# InitialTransceivers.net
KiCad netlist of a schematic drawn in EAGLE
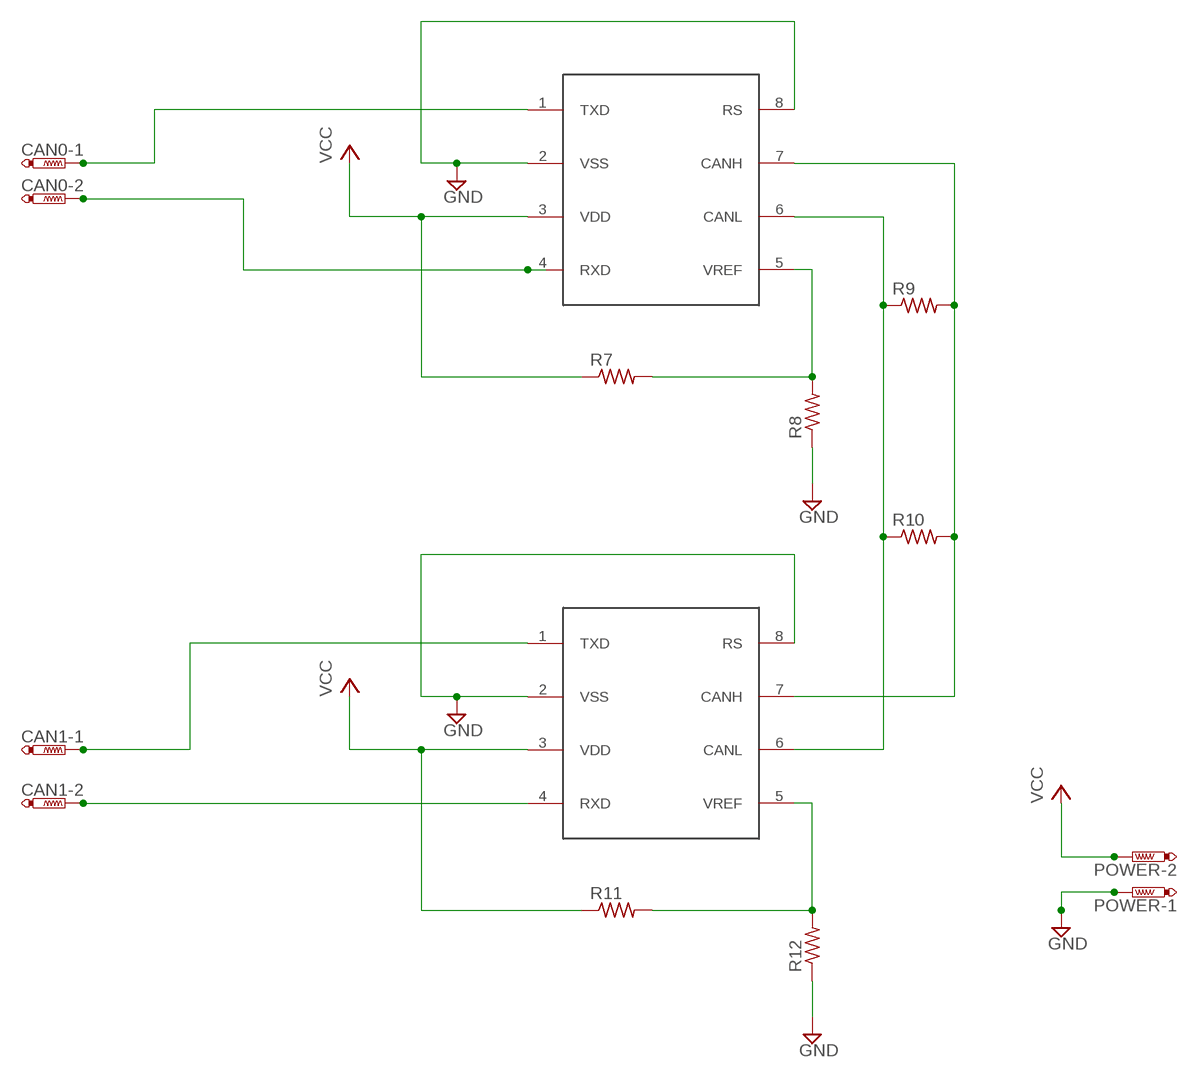
[diagram p0: schematic, sheet 1]

(export (version "E")
  (design (tool "Eeschema 10.0.6"))
  (components
    (comp (ref "CAN0")
      (value "PTR2")
      (footprint "eagle-import:P2-38-17")
      (libsource (lib "eagle-import") (part "PTR2"))
    )
    (comp (ref "CAN1")
      (value "PTR2")
      (footprint "eagle-import:P2-38-17")
      (libsource (lib "eagle-import") (part "PTR2"))
    )
    (comp (ref "POWER")
      (value "PTR2")
      (footprint "eagle-import:P2-38-17")
      (libsource (lib "eagle-import") (part "PTR2"))
    )
    (comp (ref "R7")
      (value "R-US_0204/5")
      (footprint "eagle-import:0204_5")
      (libsource (lib "eagle-import") (part "R-US_0204/5"))
    )
    (comp (ref "R8")
      (value "R-US_0204/5")
      (footprint "eagle-import:0204_5")
      (libsource (lib "eagle-import") (part "R-US_0204/5"))
    )
    (comp (ref "R9")
      (value "R-US_0204/5")
      (footprint "eagle-import:0204_5")
      (libsource (lib "eagle-import") (part "R-US_0204/5"))
    )
    (comp (ref "R10")
      (value "R-US_0204/5")
      (footprint "eagle-import:0204_5")
      (libsource (lib "eagle-import") (part "R-US_0204/5"))
    )
    (comp (ref "R11")
      (value "R-US_0204/5")
      (footprint "eagle-import:0204_5")
      (libsource (lib "eagle-import") (part "R-US_0204/5"))
    )
    (comp (ref "R12")
      (value "R-US_0204/5")
      (footprint "eagle-import:0204_5")
      (libsource (lib "eagle-import") (part "R-US_0204/5"))
    )
    (comp (ref "U$2")
      (value "MCP2551-DIP")
      (footprint "eagle-import:DIL08")
      (libsource (lib "eagle-import") (part "MCP2551-DIP"))
    )
    (comp (ref "U$3")
      (value "MCP2551-DIP")
      (footprint "eagle-import:DIL08")
      (libsource (lib "eagle-import") (part "MCP2551-DIP"))
    )
  )
  (nets
    (net (code "1") (name "GND") (class "Default")
      (node (ref "POWER") (pin "TP-1") (pinfunction "TP_TP-1") (pintype "input"))
      (node (ref "R12") (pin "1") (pinfunction "1_1") (pintype "passive"))
      (node (ref "R8") (pin "1") (pinfunction "1_1") (pintype "passive"))
      (node (ref "U$2") (pin "2") (pinfunction "VSS_2") (pintype "bidirectional"))
      (node (ref "U$2") (pin "8") (pinfunction "RS_8") (pintype "bidirectional"))
      (node (ref "U$3") (pin "2") (pinfunction "VSS_2") (pintype "bidirectional"))
      (node (ref "U$3") (pin "8") (pinfunction "RS_8") (pintype "bidirectional"))
    )
    (net (code "2") (name "Net-(CAN0A-TP)") (class "Default")
      (node (ref "CAN0") (pin "TP-1") (pinfunction "TP_TP-1") (pintype "input"))
      (node (ref "U$2") (pin "1") (pinfunction "TXD_1") (pintype "bidirectional"))
    )
    (net (code "3") (name "Net-(CAN0B-TP)") (class "Default")
      (node (ref "CAN0") (pin "TP-2") (pinfunction "TP_TP-2") (pintype "input"))
      (node (ref "U$2") (pin "4") (pinfunction "RXD_4") (pintype "bidirectional"))
    )
    (net (code "4") (name "Net-(CAN1A-TP)") (class "Default")
      (node (ref "CAN1") (pin "TP-1") (pinfunction "TP_TP-1") (pintype "input"))
      (node (ref "U$3") (pin "1") (pinfunction "TXD_1") (pintype "bidirectional"))
    )
    (net (code "5") (name "Net-(CAN1B-TP)") (class "Default")
      (node (ref "CAN1") (pin "TP-2") (pinfunction "TP_TP-2") (pintype "input"))
      (node (ref "U$3") (pin "4") (pinfunction "RXD_4") (pintype "bidirectional"))
    )
    (net (code "6") (name "Net-(U$2-CANH)") (class "Default")
      (node (ref "R10") (pin "2") (pinfunction "2_2") (pintype "passive"))
      (node (ref "R9") (pin "2") (pinfunction "2_2") (pintype "passive"))
      (node (ref "U$2") (pin "7") (pinfunction "CANH_7") (pintype "bidirectional"))
      (node (ref "U$3") (pin "7") (pinfunction "CANH_7") (pintype "bidirectional"))
    )
    (net (code "7") (name "Net-(U$2-CANL)") (class "Default")
      (node (ref "R10") (pin "1") (pinfunction "1_1") (pintype "passive"))
      (node (ref "R9") (pin "1") (pinfunction "1_1") (pintype "passive"))
      (node (ref "U$2") (pin "6") (pinfunction "CANL_6") (pintype "bidirectional"))
      (node (ref "U$3") (pin "6") (pinfunction "CANL_6") (pintype "bidirectional"))
    )
    (net (code "8") (name "Net-(U$2-VREF)") (class "Default")
      (node (ref "R7") (pin "2") (pinfunction "2_2") (pintype "passive"))
      (node (ref "R8") (pin "2") (pinfunction "2_2") (pintype "passive"))
      (node (ref "U$2") (pin "5") (pinfunction "VREF_5") (pintype "bidirectional"))
    )
    (net (code "9") (name "Net-(U$3-VREF)") (class "Default")
      (node (ref "R11") (pin "2") (pinfunction "2_2") (pintype "passive"))
      (node (ref "R12") (pin "2") (pinfunction "2_2") (pintype "passive"))
      (node (ref "U$3") (pin "5") (pinfunction "VREF_5") (pintype "bidirectional"))
    )
    (net (code "10") (name "VCC") (class "Default")
      (node (ref "POWER") (pin "TP-2") (pinfunction "TP_TP-2") (pintype "input"))
      (node (ref "R11") (pin "1") (pinfunction "1_1") (pintype "passive"))
      (node (ref "R7") (pin "1") (pinfunction "1_1") (pintype "passive"))
      (node (ref "U$2") (pin "3") (pinfunction "VDD_3") (pintype "bidirectional"))
      (node (ref "U$3") (pin "3") (pinfunction "VDD_3") (pintype "bidirectional"))
    )
  )
)
